# STM32-Flasher.net
KiCad netlist of a schematic drawn in Altium Designer
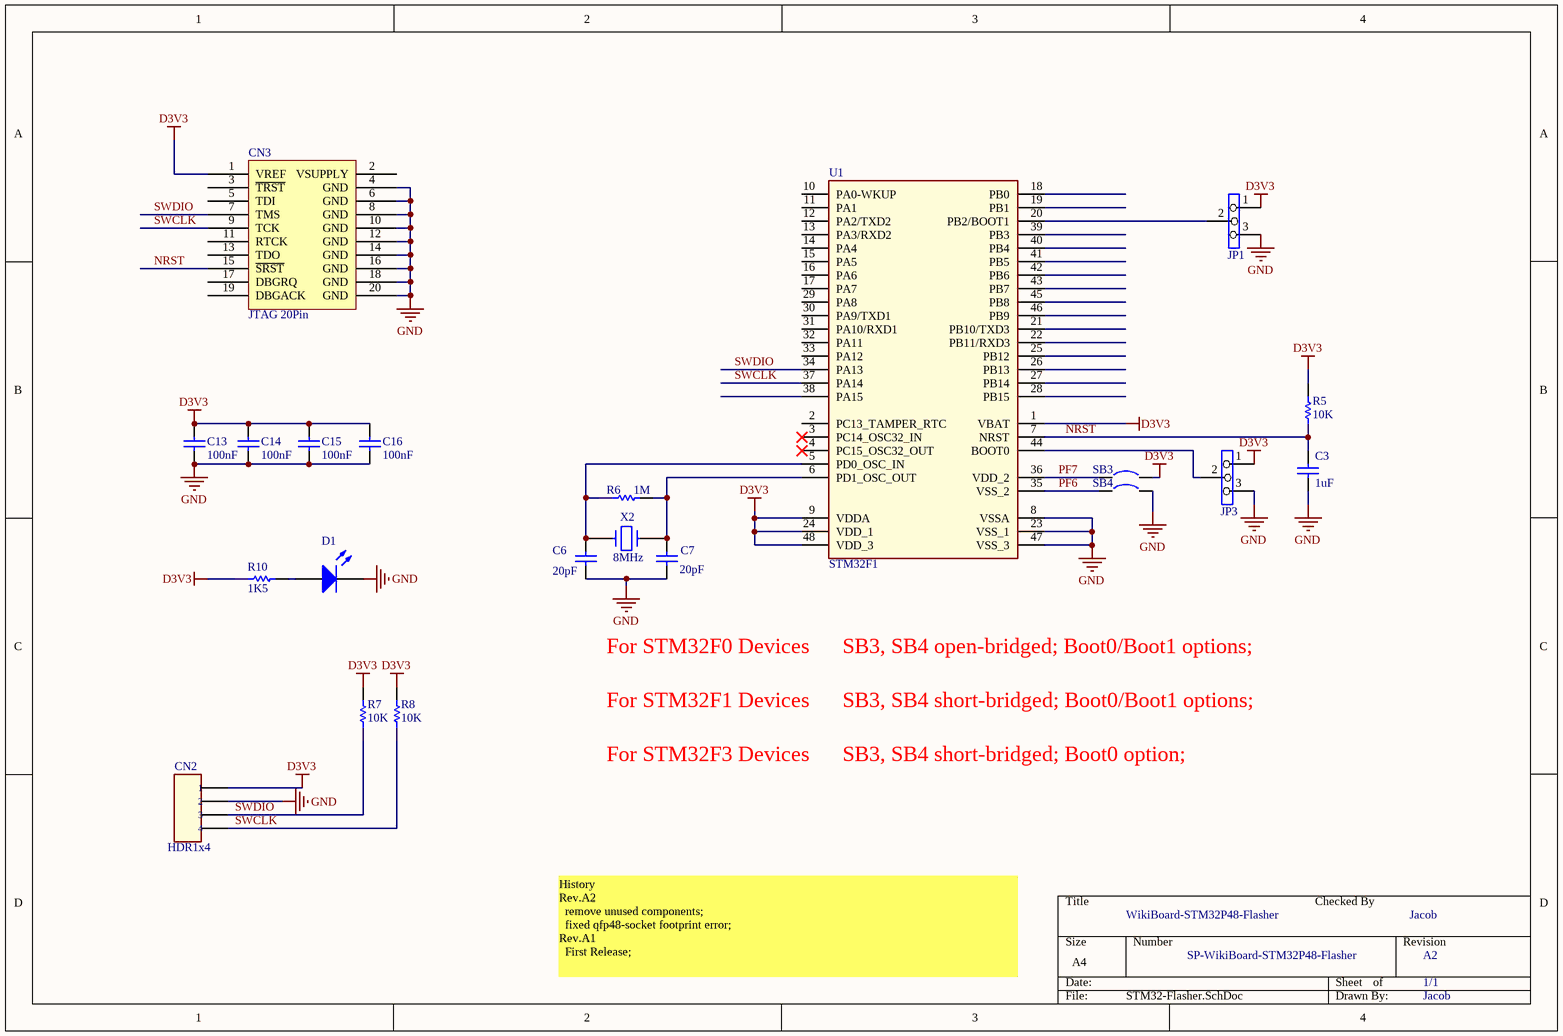
[diagram p0: STM32-Flasher.SchDoc]

(export (version "E")
  (design (tool "Eeschema 10.0.6"))
  (components
    (comp (ref "C3")
      (value "1uF")
      (footprint "C0603L")
      (description "Capacitor")
      (fields (field (name "Comment") "Cap") (field (name "PUBLISHER") "Altium Limited"))
      (libsource (lib "Miscellaneous Devices") (part "Cap"))
    )
    (comp (ref "C6")
      (value "20pF")
      (footprint "C0603L")
      (description "Capacitor")
      (fields (field (name "Comment") "Cap") (field (name "PUBLISHER") "Altium Limited"))
      (libsource (lib "Miscellaneous Devices") (part "Cap"))
    )
    (comp (ref "C7")
      (value "20pF")
      (footprint "C0603L")
      (description "Capacitor")
      (fields (field (name "Comment") "Cap") (field (name "PUBLISHER") "Altium Limited"))
      (libsource (lib "Miscellaneous Devices") (part "Cap"))
    )
    (comp (ref "C13")
      (value "100nF")
      (footprint "C0603L")
      (description "Capacitor")
      (fields (field (name "Comment") "Cap") (field (name "PUBLISHER") "Altium Limited"))
      (libsource (lib "Miscellaneous Devices") (part "Cap"))
    )
    (comp (ref "C14")
      (value "100nF")
      (footprint "C0603L")
      (description "Capacitor")
      (fields (field (name "Comment") "Cap") (field (name "PUBLISHER") "Altium Limited"))
      (libsource (lib "Miscellaneous Devices") (part "Cap"))
    )
    (comp (ref "C15")
      (value "100nF")
      (footprint "C0603L")
      (description "Capacitor")
      (fields (field (name "Comment") "Cap") (field (name "PUBLISHER") "Altium Limited"))
      (libsource (lib "Miscellaneous Devices") (part "Cap"))
    )
    (comp (ref "C16")
      (value "100nF")
      (footprint "C0603L")
      (description "Capacitor")
      (fields (field (name "Comment") "Cap") (field (name "PUBLISHER") "Altium Limited"))
      (libsource (lib "Miscellaneous Devices") (part "Cap"))
    )
    (comp (ref "CN2") (value "HDR1x4") (footprint "HDR1x4") (libsource (lib "Mylib") (part "CON4")))
    (comp (ref "CN3")
      (value "JTAG 20Pin")
      (footprint "DC3/20P/2.54mm")
      (description "20Pin JTAG CONNECTOR")
      (libsource (lib "Connector") (part "JTAG 20Pin"))
    )
    (comp (ref "D1")
      (value "LED1")
      (footprint "0603pn")
      (description "Typical RED GaAs LED")
      (fields (field (name "PUBLISHER") "Altium Limited"))
      (libsource (lib "Studio") (part "LED1"))
    )
    (comp (ref "JP1") (value "Jumper3") (footprint "HDR1X3/2.54MM") (libsource (lib "Misc") (part "Jumper3")))
    (comp (ref "JP3") (value "Jumper3") (footprint "HDR1X3/2.54MM") (libsource (lib "Misc") (part "Jumper3")))
    (comp (ref "R5")
      (value "10K")
      (footprint "R0603")
      (description "Resistor")
      (libsource (lib "Mylib") (part "RES"))
    )
    (comp (ref "R6")
      (value "1M")
      (footprint "R0603")
      (description "Resistor")
      (libsource (lib "Mylib") (part "RES"))
    )
    (comp (ref "R7")
      (value "10K")
      (footprint "R0603")
      (description "Resistor")
      (libsource (lib "Mylib") (part "RES"))
    )
    (comp (ref "R8")
      (value "10K")
      (footprint "R0603")
      (description "Resistor")
      (libsource (lib "Mylib") (part "RES"))
    )
    (comp (ref "R10")
      (value "1K5")
      (footprint "R0603")
      (description "Resistor")
      (libsource (lib "Mylib") (part "RES"))
    )
    (comp (ref "SB3")
      (value "Circuit Breaker")
      (footprint "HDR1X2/2.54mm")
      (fields (field (name "PUBLISHER") "Altium Limited"))
      (libsource (lib "MB915") (part "Circuit Breaker"))
    )
    (comp (ref "SB4")
      (value "Circuit Breaker")
      (footprint "HDR1X2/2.54mm")
      (fields (field (name "PUBLISHER") "Altium Limited"))
      (libsource (lib "MB915") (part "Circuit Breaker"))
    )
    (comp (ref "U1")
      (value "STM32F1")
      (footprint "QFP48-Socket")
      (description "Cortex M3, 48-pin LQFP")
      (libsource (lib "Processor") (part "STM32F103CxT"))
    )
    (comp (ref "X2")
      (value "8MHz")
      (footprint "XTAL_socket")
      (description "Crystal")
      (libsource (lib "*") (part "CRYSTAL"))
    )
  )
  (nets
    (net (code "1") (name "/NRST") (class "Default")
      (node (ref "C3") (pin "2") (pinfunction "2_2") (pintype "passive"))
      (node (ref "CN3") (pin "15") (pinfunction "~{SRST}_15") (pintype "passive"))
      (node (ref "R5") (pin "1") (pinfunction "1_1") (pintype "passive"))
      (node (ref "U1") (pin "7") (pinfunction "NRST_7") (pintype "passive"))
    )
    (net (code "2") (name "/PF6") (class "Default")
      (node (ref "SB4") (pin "1") (pinfunction "1_1") (pintype "passive"))
      (node (ref "U1") (pin "35") (pinfunction "VSS_2_35") (pintype "passive"))
    )
    (net (code "3") (name "/PF7") (class "Default")
      (node (ref "SB3") (pin "1") (pinfunction "1_1") (pintype "passive"))
      (node (ref "U1") (pin "36") (pinfunction "VDD_2_36") (pintype "passive"))
    )
    (net (code "4") (name "/SWCLK") (class "Default")
      (node (ref "CN2") (pin "4") (pinfunction "4_4") (pintype "passive"))
      (node (ref "CN3") (pin "9") (pinfunction "TCK_9") (pintype "passive"))
      (node (ref "R8") (pin "1") (pinfunction "1_1") (pintype "passive"))
      (node (ref "U1") (pin "37") (pinfunction "PA14_37") (pintype "passive"))
    )
    (net (code "5") (name "/SWDIO") (class "Default")
      (node (ref "CN2") (pin "3") (pinfunction "3_3") (pintype "passive"))
      (node (ref "CN3") (pin "7") (pinfunction "TMS_7") (pintype "passive"))
      (node (ref "R7") (pin "1") (pinfunction "1_1") (pintype "passive"))
      (node (ref "U1") (pin "34") (pinfunction "PA13_34") (pintype "passive"))
    )
    (net (code "6") (name "D3V3") (class "Default")
      (node (ref "C13") (pin "2") (pinfunction "2_2") (pintype "passive"))
      (node (ref "C14") (pin "2") (pinfunction "2_2") (pintype "passive"))
      (node (ref "C15") (pin "2") (pinfunction "2_2") (pintype "passive"))
      (node (ref "C16") (pin "2") (pinfunction "2_2") (pintype "passive"))
      (node (ref "CN2") (pin "1") (pinfunction "1_1") (pintype "passive"))
      (node (ref "CN3") (pin "1") (pinfunction "VREF_1") (pintype "passive"))
      (node (ref "JP1") (pin "1") (pintype "passive"))
      (node (ref "JP3") (pin "1") (pintype "passive"))
      (node (ref "R10") (pin "1") (pinfunction "1_1") (pintype "passive"))
      (node (ref "R5") (pin "2") (pinfunction "2_2") (pintype "passive"))
      (node (ref "R7") (pin "2") (pinfunction "2_2") (pintype "passive"))
      (node (ref "R8") (pin "2") (pinfunction "2_2") (pintype "passive"))
      (node (ref "SB3") (pin "2") (pinfunction "2_2") (pintype "passive"))
      (node (ref "U1") (pin "1") (pinfunction "VBAT_1") (pintype "passive"))
      (node (ref "U1") (pin "24") (pinfunction "VDD_1_24") (pintype "passive"))
      (node (ref "U1") (pin "48") (pinfunction "VDD_3_48") (pintype "passive"))
      (node (ref "U1") (pin "9") (pinfunction "VDDA_9") (pintype "passive"))
    )
    (net (code "7") (name "GND") (class "Default")
      (node (ref "C13") (pin "1") (pinfunction "1_1") (pintype "passive"))
      (node (ref "C14") (pin "1") (pinfunction "1_1") (pintype "passive"))
      (node (ref "C15") (pin "1") (pinfunction "1_1") (pintype "passive"))
      (node (ref "C16") (pin "1") (pinfunction "1_1") (pintype "passive"))
      (node (ref "C3") (pin "1") (pinfunction "1_1") (pintype "passive"))
      (node (ref "C6") (pin "1") (pinfunction "1_1") (pintype "passive"))
      (node (ref "C7") (pin "1") (pinfunction "1_1") (pintype "passive"))
      (node (ref "CN2") (pin "2") (pinfunction "2_2") (pintype "passive"))
      (node (ref "CN3") (pin "10") (pinfunction "GND_10") (pintype "passive"))
      (node (ref "CN3") (pin "12") (pinfunction "GND_12") (pintype "passive"))
      (node (ref "CN3") (pin "14") (pinfunction "GND_14") (pintype "passive"))
      (node (ref "CN3") (pin "16") (pinfunction "GND_16") (pintype "passive"))
      (node (ref "CN3") (pin "18") (pinfunction "GND_18") (pintype "passive"))
      (node (ref "CN3") (pin "20") (pinfunction "GND_20") (pintype "passive"))
      (node (ref "CN3") (pin "4") (pinfunction "GND_4") (pintype "passive"))
      (node (ref "CN3") (pin "6") (pinfunction "GND_6") (pintype "passive"))
      (node (ref "CN3") (pin "8") (pinfunction "GND_8") (pintype "passive"))
      (node (ref "D1") (pin "2") (pinfunction "K_2") (pintype "passive"))
      (node (ref "JP1") (pin "3") (pintype "passive"))
      (node (ref "JP3") (pin "3") (pintype "passive"))
      (node (ref "SB4") (pin "2") (pinfunction "2_2") (pintype "passive"))
      (node (ref "U1") (pin "23") (pinfunction "VSS_1_23") (pintype "passive"))
      (node (ref "U1") (pin "47") (pinfunction "VSS_3_47") (pintype "passive"))
      (node (ref "U1") (pin "8") (pinfunction "VSSA_8") (pintype "passive"))
    )
    (net (code "8") (name "Net-(D1-A)") (class "Default")
      (node (ref "D1") (pin "1") (pinfunction "A_1") (pintype "passive"))
      (node (ref "R10") (pin "2") (pinfunction "2_2") (pintype "passive"))
    )
    (net (code "9") (name "Net-(U1-BOOT0)") (class "Default")
      (node (ref "JP3") (pin "2") (pintype "passive"))
      (node (ref "U1") (pin "44") (pinfunction "BOOT0_44") (pintype "passive"))
    )
    (net (code "10") (name "Net-(U1-PB2{slash}BOOT1)") (class "Default")
      (node (ref "JP1") (pin "2") (pintype "passive"))
      (node (ref "U1") (pin "20") (pinfunction "PB2/BOOT1_20") (pintype "passive"))
    )
    (net (code "11") (name "Net-(U1-PD0_OSC_IN)") (class "Default")
      (node (ref "C6") (pin "2") (pinfunction "2_2") (pintype "passive"))
      (node (ref "R6") (pin "1") (pinfunction "1_1") (pintype "passive"))
      (node (ref "U1") (pin "5") (pinfunction "PD0_OSC_IN_5") (pintype "passive"))
      (node (ref "X2") (pin "2") (pinfunction "2_2") (pintype "passive"))
    )
    (net (code "12") (name "Net-(U1-PD1_OSC_OUT)") (class "Default")
      (node (ref "C7") (pin "2") (pinfunction "2_2") (pintype "passive"))
      (node (ref "R6") (pin "2") (pinfunction "2_2") (pintype "passive"))
      (node (ref "U1") (pin "6") (pinfunction "PD1_OSC_OUT_6") (pintype "passive"))
      (node (ref "X2") (pin "1") (pinfunction "1_1") (pintype "passive"))
    )
    (net (code "13") (name "unconnected-(CN3-DBGACK-Pad19)") (class "Default")
      (node (ref "CN3") (pin "19") (pinfunction "DBGACK_19") (pintype "passive"))
    )
    (net (code "14") (name "unconnected-(CN3-DBGRQ-Pad17)") (class "Default")
      (node (ref "CN3") (pin "17") (pinfunction "DBGRQ_17") (pintype "passive"))
    )
    (net (code "15") (name "unconnected-(CN3-RTCK-Pad11)") (class "Default")
      (node (ref "CN3") (pin "11") (pinfunction "RTCK_11") (pintype "passive"))
    )
    (net (code "16") (name "unconnected-(CN3-TDI-Pad5)") (class "Default")
      (node (ref "CN3") (pin "5") (pinfunction "TDI_5") (pintype "passive"))
    )
    (net (code "17") (name "unconnected-(CN3-TDO-Pad13)") (class "Default")
      (node (ref "CN3") (pin "13") (pinfunction "TDO_13") (pintype "passive"))
    )
    (net (code "18") (name "unconnected-(CN3-VSUPPLY-Pad2)") (class "Default")
      (node (ref "CN3") (pin "2") (pinfunction "VSUPPLY_2") (pintype "passive"))
    )
    (net (code "19") (name "unconnected-(CN3-~{TRST}-Pad3)") (class "Default")
      (node (ref "CN3") (pin "3") (pinfunction "~{TRST}_3") (pintype "passive"))
    )
    (net (code "20") (name "unconnected-(U1-PA0-WKUP-Pad10)") (class "Default")
      (node (ref "U1") (pin "10") (pinfunction "PA0-WKUP_10") (pintype "passive"))
    )
    (net (code "21") (name "unconnected-(U1-PA1-Pad11)") (class "Default")
      (node (ref "U1") (pin "11") (pinfunction "PA1_11") (pintype "passive"))
    )
    (net (code "22") (name "unconnected-(U1-PA2{slash}TXD2-Pad12)") (class "Default")
      (node (ref "U1") (pin "12") (pinfunction "PA2/TXD2_12") (pintype "passive"))
    )
    (net (code "23") (name "unconnected-(U1-PA3{slash}RXD2-Pad13)") (class "Default")
      (node (ref "U1") (pin "13") (pinfunction "PA3/RXD2_13") (pintype "passive"))
    )
    (net (code "24") (name "unconnected-(U1-PA4-Pad14)") (class "Default")
      (node (ref "U1") (pin "14") (pinfunction "PA4_14") (pintype "passive"))
    )
    (net (code "25") (name "unconnected-(U1-PA5-Pad15)") (class "Default")
      (node (ref "U1") (pin "15") (pinfunction "PA5_15") (pintype "passive"))
    )
    (net (code "26") (name "unconnected-(U1-PA6-Pad16)") (class "Default")
      (node (ref "U1") (pin "16") (pinfunction "PA6_16") (pintype "passive"))
    )
    (net (code "27") (name "unconnected-(U1-PA7-Pad17)") (class "Default")
      (node (ref "U1") (pin "17") (pinfunction "PA7_17") (pintype "passive"))
    )
    (net (code "28") (name "unconnected-(U1-PA8-Pad29)") (class "Default")
      (node (ref "U1") (pin "29") (pinfunction "PA8_29") (pintype "passive"))
    )
    (net (code "29") (name "unconnected-(U1-PA9{slash}TXD1-Pad30)") (class "Default")
      (node (ref "U1") (pin "30") (pinfunction "PA9/TXD1_30") (pintype "passive"))
    )
    (net (code "30") (name "unconnected-(U1-PA10{slash}RXD1-Pad31)") (class "Default")
      (node (ref "U1") (pin "31") (pinfunction "PA10/RXD1_31") (pintype "passive"))
    )
    (net (code "31") (name "unconnected-(U1-PA11-Pad32)") (class "Default")
      (node (ref "U1") (pin "32") (pinfunction "PA11_32") (pintype "passive"))
    )
    (net (code "32") (name "unconnected-(U1-PA12-Pad33)") (class "Default")
      (node (ref "U1") (pin "33") (pinfunction "PA12_33") (pintype "passive"))
    )
    (net (code "33") (name "unconnected-(U1-PA15-Pad38)") (class "Default")
      (node (ref "U1") (pin "38") (pinfunction "PA15_38") (pintype "passive"))
    )
    (net (code "34") (name "unconnected-(U1-PB0-Pad18)") (class "Default")
      (node (ref "U1") (pin "18") (pinfunction "PB0_18") (pintype "passive"))
    )
    (net (code "35") (name "unconnected-(U1-PB1-Pad19)") (class "Default")
      (node (ref "U1") (pin "19") (pinfunction "PB1_19") (pintype "passive"))
    )
    (net (code "36") (name "unconnected-(U1-PB3-Pad39)") (class "Default")
      (node (ref "U1") (pin "39") (pinfunction "PB3_39") (pintype "passive"))
    )
    (net (code "37") (name "unconnected-(U1-PB4-Pad40)") (class "Default")
      (node (ref "U1") (pin "40") (pinfunction "PB4_40") (pintype "passive"))
    )
    (net (code "38") (name "unconnected-(U1-PB5-Pad41)") (class "Default")
      (node (ref "U1") (pin "41") (pinfunction "PB5_41") (pintype "passive"))
    )
    (net (code "39") (name "unconnected-(U1-PB6-Pad42)") (class "Default")
      (node (ref "U1") (pin "42") (pinfunction "PB6_42") (pintype "passive"))
    )
    (net (code "40") (name "unconnected-(U1-PB7-Pad43)") (class "Default")
      (node (ref "U1") (pin "43") (pinfunction "PB7_43") (pintype "passive"))
    )
    (net (code "41") (name "unconnected-(U1-PB8-Pad45)") (class "Default")
      (node (ref "U1") (pin "45") (pinfunction "PB8_45") (pintype "passive"))
    )
    (net (code "42") (name "unconnected-(U1-PB9-Pad46)") (class "Default")
      (node (ref "U1") (pin "46") (pinfunction "PB9_46") (pintype "passive"))
    )
    (net (code "43") (name "unconnected-(U1-PB10{slash}TXD3-Pad21)") (class "Default")
      (node (ref "U1") (pin "21") (pinfunction "PB10/TXD3_21") (pintype "passive"))
    )
    (net (code "44") (name "unconnected-(U1-PB11{slash}RXD3-Pad22)") (class "Default")
      (node (ref "U1") (pin "22") (pinfunction "PB11/RXD3_22") (pintype "passive"))
    )
    (net (code "45") (name "unconnected-(U1-PB12-Pad25)") (class "Default")
      (node (ref "U1") (pin "25") (pinfunction "PB12_25") (pintype "passive"))
    )
    (net (code "46") (name "unconnected-(U1-PB13-Pad26)") (class "Default")
      (node (ref "U1") (pin "26") (pinfunction "PB13_26") (pintype "passive"))
    )
    (net (code "47") (name "unconnected-(U1-PB14-Pad27)") (class "Default")
      (node (ref "U1") (pin "27") (pinfunction "PB14_27") (pintype "passive"))
    )
    (net (code "48") (name "unconnected-(U1-PB15-Pad28)") (class "Default")
      (node (ref "U1") (pin "28") (pinfunction "PB15_28") (pintype "passive"))
    )
    (net (code "49") (name "unconnected-(U1-PC13_TAMPER_RTC-Pad2)") (class "Default")
      (node (ref "U1") (pin "2") (pinfunction "PC13_TAMPER_RTC_2") (pintype "passive"))
    )
    (net (code "50") (name "unconnected-(U1-PC14_OSC32_IN-Pad3)") (class "Default")
      (node (ref "U1") (pin "3") (pinfunction "PC14_OSC32_IN_3") (pintype "passive+no_connect"))
    )
    (net (code "51") (name "unconnected-(U1-PC15_OSC32_OUT-Pad4)") (class "Default")
      (node (ref "U1") (pin "4") (pinfunction "PC15_OSC32_OUT_4") (pintype "passive+no_connect"))
    )
  )
)
